# comparator.net
KiCad netlist of a schematic drawn in Altium Designer
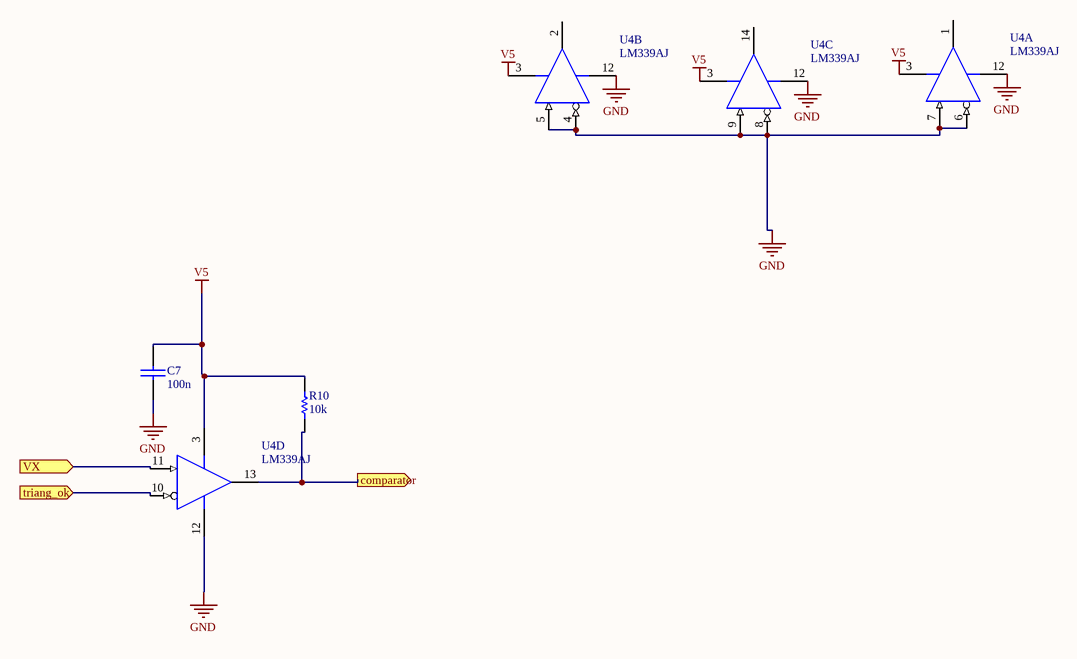
[diagram p0: comparator.SchDoc]

(export (version "E")
  (design (tool "Eeschema 10.0.6"))
  (components
    (comp (ref "C7") (value "100n") (footprint "CAP200") (libsource (lib "LIBEBAL") (part "CAP")))
    (comp (ref "R10") (value "10k") (footprint "RES400") (libsource (lib "LIBEBAL") (part "RES")))
    (comp (ref "U4")
      (value "LM339AJ")
      (footprint "J014")
      (description "Quad Differential Comparator")
      (fields (field (name "PUBLISHER") "Altium Limited"))
      (libsource (lib "TI Analog Comparator") (part "LM339AJ"))
    )
  )
  (nets
    (net (code "1") (name "/VX") (class "Default")
      (node (ref "U4") (pin "11") (pinfunction "IN+_11") (pintype "input"))
    )
    (net (code "2") (name "/comparator") (class "Default")
      (node (ref "R10") (pin "1") (pinfunction "1_1") (pintype "passive"))
      (node (ref "U4") (pin "13") (pinfunction "OUT_13") (pintype "open_collector"))
    )
    (net (code "3") (name "/triang_ok") (class "Default")
      (node (ref "U4") (pin "10") (pinfunction "IN-_10") (pintype "input"))
    )
    (net (code "4") (name "GND") (class "Default")
      (node (ref "C7") (pin "2") (pinfunction "2_2") (pintype "passive"))
      (node (ref "U4") (pin "12") (pinfunction "GND_12") (pintype "power_in"))
      (node (ref "U4") (pin "4") (pinfunction "IN-_4") (pintype "input"))
      (node (ref "U4") (pin "5") (pinfunction "IN+_5") (pintype "input"))
      (node (ref "U4") (pin "6") (pinfunction "IN-_6") (pintype "input"))
      (node (ref "U4") (pin "7") (pinfunction "IN+_7") (pintype "input"))
      (node (ref "U4") (pin "8") (pinfunction "IN-_8") (pintype "input"))
      (node (ref "U4") (pin "9") (pinfunction "IN+_9") (pintype "input"))
    )
    (net (code "5") (name "V5") (class "Default")
      (node (ref "C7") (pin "1") (pinfunction "1_1") (pintype "passive"))
      (node (ref "R10") (pin "2") (pinfunction "2_2") (pintype "passive"))
      (node (ref "U4") (pin "3") (pinfunction "VCC_3") (pintype "power_in"))
    )
    (net (code "6") (name "unconnected-(U4A-OUT-Pad1)") (class "Default")
      (node (ref "U4") (pin "1") (pinfunction "OUT_1") (pintype "open_collector"))
    )
    (net (code "7") (name "unconnected-(U4B-OUT-Pad2)") (class "Default")
      (node (ref "U4") (pin "2") (pinfunction "OUT_2") (pintype "open_collector"))
    )
    (net (code "8") (name "unconnected-(U4C-OUT-Pad14)") (class "Default")
      (node (ref "U4") (pin "14") (pinfunction "OUT_14") (pintype "open_collector"))
    )
  )
)
